# LIA_slave.net
KiCad netlist of a schematic drawn in Altium Designer
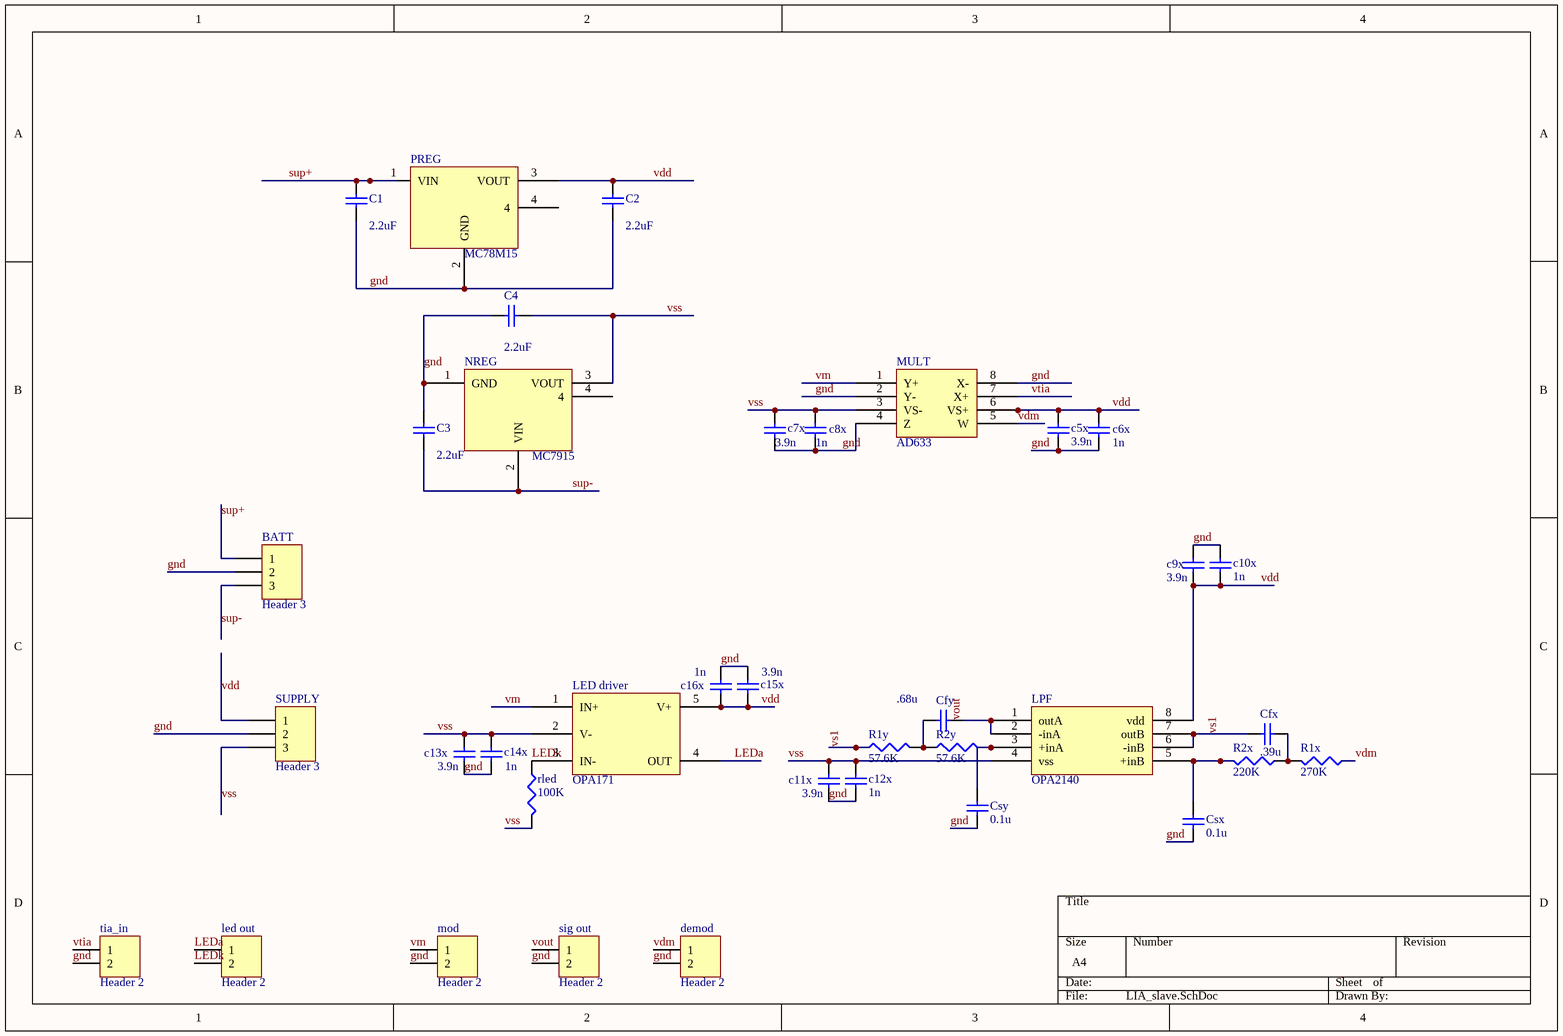
[diagram p0: LIA_slave.SchDoc]

(export (version "E")
  (design (tool "Eeschema 10.0.6"))
  (components
    (comp (ref "BATT")
      (value "Header 3")
      (footprint "HDR1X3")
      (description "Header, 3-Pin")
      (fields (field (name "PUBLISHER") "Altium Limited"))
      (libsource (lib "Miscellaneous Connectors") (part "Header 3"))
    )
    (comp (ref "C1")
      (value "2.2uF")
      (footprint "0402")
      (description "Ceramic Chip Capacitor - Standard")
      (fields (field (name "Comment") "GRM155R61C225KE11D") (field (name "PUBLISHER") "Altium Limited"))
      (libsource (lib "KEMET Chip Capacitor") (part "C0402"))
    )
    (comp (ref "C2")
      (value "2.2uF")
      (footprint "0402")
      (description "Ceramic Chip Capacitor - Standard")
      (fields (field (name "Comment") "GRM155R61C225KE11D") (field (name "PUBLISHER") "Altium Limited"))
      (libsource (lib "KEMET Chip Capacitor") (part "C0402"))
    )
    (comp (ref "C3")
      (value "2.2uF")
      (footprint "0402")
      (description "Ceramic Chip Capacitor - Standard")
      (fields (field (name "Comment") "GRM155R61C225KE11D") (field (name "PUBLISHER") "Altium Limited"))
      (libsource (lib "KEMET Chip Capacitor") (part "C0402"))
    )
    (comp (ref "C4")
      (value "2.2uF")
      (footprint "0402")
      (description "Ceramic Chip Capacitor - Standard")
      (fields (field (name "Comment") "GRM155R61C225KE11D") (field (name "PUBLISHER") "Altium Limited"))
      (libsource (lib "KEMET Chip Capacitor") (part "C0402"))
    )
    (comp (ref "c5x")
      (value "3.9n")
      (footprint "0402")
      (description "Ceramic Chip Capacitor - Standard")
      (fields (field (name "Comment") "GRM155R71H392KA01D") (field (name "PUBLISHER") "Altium Limited"))
      (libsource (lib "KEMET Chip Capacitor") (part "C0402"))
    )
    (comp (ref "c6x")
      (value "1n")
      (footprint "0402")
      (description "Ceramic Chip Capacitor - Standard")
      (fields (field (name "Comment") "GRM155R71H102KA01D") (field (name "PUBLISHER") "Altium Limited"))
      (libsource (lib "KEMET Chip Capacitor") (part "C0402"))
    )
    (comp (ref "c7x")
      (value "3.9n")
      (footprint "0402")
      (description "Ceramic Chip Capacitor - Standard")
      (fields (field (name "Comment") "GRM155R71H392KA01D") (field (name "PUBLISHER") "Altium Limited"))
      (libsource (lib "KEMET Chip Capacitor") (part "C0402"))
    )
    (comp (ref "c8x")
      (value "1n")
      (footprint "0402")
      (description "Ceramic Chip Capacitor - Standard")
      (fields (field (name "Comment") "GRM155R71H102KA01D") (field (name "PUBLISHER") "Altium Limited"))
      (libsource (lib "KEMET Chip Capacitor") (part "C0402"))
    )
    (comp (ref "c9x")
      (value "3.9n")
      (footprint "0402")
      (description "Ceramic Chip Capacitor - Standard")
      (fields (field (name "Comment") "GRM155R71H392KA01D") (field (name "PUBLISHER") "Altium Limited"))
      (libsource (lib "KEMET Chip Capacitor") (part "C0402"))
    )
    (comp (ref "c10x")
      (value "1n")
      (footprint "0402")
      (description "Ceramic Chip Capacitor - Standard")
      (fields (field (name "Comment") "GRM155R71H102KA01D") (field (name "PUBLISHER") "Altium Limited"))
      (libsource (lib "KEMET Chip Capacitor") (part "C0402"))
    )
    (comp (ref "c11x")
      (value "3.9n")
      (footprint "0402")
      (description "Ceramic Chip Capacitor - Standard")
      (fields (field (name "Comment") "GRM155R71H392KA01D") (field (name "PUBLISHER") "Altium Limited"))
      (libsource (lib "KEMET Chip Capacitor") (part "C0402"))
    )
    (comp (ref "c12x")
      (value "1n")
      (footprint "0402")
      (description "Ceramic Chip Capacitor - Standard")
      (fields (field (name "Comment") "GRM155R71H102KA01D") (field (name "PUBLISHER") "Altium Limited"))
      (libsource (lib "KEMET Chip Capacitor") (part "C0402"))
    )
    (comp (ref "c13x")
      (value "3.9n")
      (footprint "0402")
      (description "Ceramic Chip Capacitor - Standard")
      (fields (field (name "Comment") "GRM155R71H392KA01D") (field (name "PUBLISHER") "Altium Limited"))
      (libsource (lib "KEMET Chip Capacitor") (part "C0402"))
    )
    (comp (ref "c14x")
      (value "1n")
      (footprint "0402")
      (description "Ceramic Chip Capacitor - Standard")
      (fields (field (name "Comment") "GRM155R71H102KA01D") (field (name "PUBLISHER") "Altium Limited"))
      (libsource (lib "KEMET Chip Capacitor") (part "C0402"))
    )
    (comp (ref "c15x")
      (value "3.9n")
      (footprint "0402")
      (description "Ceramic Chip Capacitor - Standard")
      (fields (field (name "Comment") "GRM155R71H392KA01D") (field (name "PUBLISHER") "Altium Limited"))
      (libsource (lib "KEMET Chip Capacitor") (part "C0402"))
    )
    (comp (ref "c16x")
      (value "1n")
      (footprint "0402")
      (description "Ceramic Chip Capacitor - Standard")
      (fields (field (name "Comment") "GRM155R71H102KA01D") (field (name "PUBLISHER") "Altium Limited"))
      (libsource (lib "KEMET Chip Capacitor") (part "C0402"))
    )
    (comp (ref "Cfx")
      (value ".39u")
      (footprint "0402")
      (description "Ceramic Chip Capacitor - Standard")
      (fields (field (name "Comment") "GRM155R61A394KE15D") (field (name "PUBLISHER") "Altium Limited"))
      (libsource (lib "KEMET Chip Capacitor") (part "C0402"))
    )
    (comp (ref "Cfy")
      (value ".68u")
      (footprint "0402")
      (description "Ceramic Chip Capacitor - Standard")
      (fields (field (name "Comment") "C1005X5R1C684K050BC") (field (name "PUBLISHER") "Altium Limited"))
      (libsource (lib "KEMET Chip Capacitor") (part "C0402"))
    )
    (comp (ref "Csx")
      (value "0.1u")
      (footprint "0402")
      (description "Ceramic Chip Capacitor - Standard")
      (fields (field (name "Comment") "GRM155R61C104KA88J") (field (name "PUBLISHER") "Altium Limited"))
      (libsource (lib "KEMET Chip Capacitor") (part "C0402"))
    )
    (comp (ref "Csy")
      (value "0.1u")
      (footprint "0402")
      (description "Ceramic Chip Capacitor - Standard")
      (fields (field (name "Comment") "GRM155R61C104KA88J") (field (name "PUBLISHER") "Altium Limited"))
      (libsource (lib "KEMET Chip Capacitor") (part "C0402"))
    )
    (comp (ref "demod")
      (value "Header 2")
      (footprint "HDR1X2")
      (description "Header, 2-Pin")
      (fields (field (name "PUBLISHER") "Altium Limited"))
      (libsource (lib "Miscellaneous Connectors") (part "Header 2"))
    )
    (comp (ref "LED driver")
      (value "OPA171")
      (footprint "S5")
      (description "Single supply opamp SOT 553")
      (libsource (lib "katschematic") (part "OPA171"))
    )
    (comp (ref "led out")
      (value "Header 2")
      (footprint "HDR1X2")
      (description "Header, 2-Pin")
      (fields (field (name "PUBLISHER") "Altium Limited"))
      (libsource (lib "Miscellaneous Connectors") (part "Header 2"))
    )
    (comp (ref "LPF")
      (value "OPA2140")
      (description "dual channel JFET op amp")
      (libsource (lib "Schlib1") (part "OPA2211"))
    )
    (comp (ref "mod")
      (value "Header 2")
      (footprint "HDR1X2")
      (description "Header, 2-Pin")
      (fields (field (name "PUBLISHER") "Altium Limited"))
      (libsource (lib "Miscellaneous Connectors") (part "Header 2"))
    )
    (comp (ref "MULT")
      (value "AD633")
      (footprint "D008_L")
      (description "Analog multiplier")
      (libsource (lib "katschematic") (part "AD633"))
    )
    (comp (ref "NREG")
      (value "MC7915")
      (footprint "D2PAK_L")
      (description "-15 V LDO regulator")
      (libsource (lib "katschematic") (part "MC7915"))
    )
    (comp (ref "PREG")
      (value "MC78M15")
      (footprint "D2PAK_L")
      (description "+15 V LDO regulator")
      (libsource (lib "katschematic") (part "MC78M15"))
    )
    (comp (ref "R1x")
      (value "270K")
      (footprint "J1-0603")
      (description "Resistor")
      (fields (field (name "Comment") "RC0603FR-07270KL") (field (name "PUBLISHER") "Altium Limited"))
      (libsource (lib "Miscellaneous Devices") (part "Res3"))
    )
    (comp (ref "R1y")
      (value "57.6K")
      (footprint "J1-0603")
      (description "Resistor")
      (fields (field (name "Comment") "RC0603FR-0757K6L") (field (name "PUBLISHER") "Altium Limited"))
      (libsource (lib "Miscellaneous Devices") (part "Res3"))
    )
    (comp (ref "R2x")
      (value "220K")
      (footprint "J1-0603")
      (description "Resistor")
      (fields (field (name "Comment") "RC0603FR-07220KL") (field (name "PUBLISHER") "Altium Limited"))
      (libsource (lib "Miscellaneous Devices") (part "Res3"))
    )
    (comp (ref "R2y")
      (value "57.6K")
      (footprint "J1-0603")
      (description "Resistor")
      (fields (field (name "Comment") "RC0603FR-0757K6L") (field (name "PUBLISHER") "Altium Limited"))
      (libsource (lib "Miscellaneous Devices") (part "Res3"))
    )
    (comp (ref "rled")
      (value "100K")
      (footprint "J1-0603")
      (description "Resistor")
      (fields (field (name "Comment") "RC0603FR-07100KL") (field (name "PUBLISHER") "Altium Limited"))
      (libsource (lib "Miscellaneous Devices") (part "Res3"))
    )
    (comp (ref "sig out")
      (value "Header 2")
      (footprint "HDR1X2")
      (description "Header, 2-Pin")
      (fields (field (name "PUBLISHER") "Altium Limited"))
      (libsource (lib "Miscellaneous Connectors") (part "Header 2"))
    )
    (comp (ref "SUPPLY")
      (value "Header 3")
      (footprint "HDR1X3")
      (description "Header, 3-Pin")
      (fields (field (name "PUBLISHER") "Altium Limited"))
      (libsource (lib "Miscellaneous Connectors") (part "Header 3"))
    )
    (comp (ref "tia_in")
      (value "Header 2")
      (footprint "HDR1X2")
      (description "Header, 2-Pin")
      (fields (field (name "PUBLISHER") "Altium Limited"))
      (libsource (lib "Miscellaneous Connectors") (part "Header 2"))
    )
  )
  (nets
    (net (code "1") (name "/LEDa") (class "Default")
      (node (ref "LED driver") (pin "4") (pinfunction "OUT_4") (pintype "passive"))
      (node (ref "led out") (pin "1") (pinfunction "1_1") (pintype "passive"))
    )
    (net (code "2") (name "/LEDk") (class "Default")
      (node (ref "LED driver") (pin "3") (pinfunction "IN-_3") (pintype "passive"))
      (node (ref "led out") (pin "2") (pinfunction "2_2") (pintype "passive"))
      (node (ref "rled") (pin "1") (pinfunction "1_1") (pintype "passive"))
    )
    (net (code "3") (name "/gnd") (class "Default")
      (node (ref "BATT") (pin "2") (pinfunction "2_2") (pintype "passive"))
      (node (ref "C1") (pin "1") (pinfunction "1_1") (pintype "passive"))
      (node (ref "C2") (pin "1") (pinfunction "1_1") (pintype "passive"))
      (node (ref "C3") (pin "1") (pinfunction "1_1") (pintype "passive"))
      (node (ref "C4") (pin "1") (pinfunction "1_1") (pintype "passive"))
      (node (ref "Csx") (pin "1") (pinfunction "1_1") (pintype "passive"))
      (node (ref "Csy") (pin "1") (pinfunction "1_1") (pintype "passive"))
      (node (ref "MULT") (pin "2") (pinfunction "Y-_2") (pintype "passive"))
      (node (ref "MULT") (pin "4") (pinfunction "Z_4") (pintype "passive"))
      (node (ref "MULT") (pin "8") (pinfunction "X-_8") (pintype "passive"))
      (node (ref "NREG") (pin "1") (pinfunction "GND_1") (pintype "passive"))
      (node (ref "PREG") (pin "2") (pinfunction "GND_2") (pintype "passive"))
      (node (ref "SUPPLY") (pin "2") (pinfunction "2_2") (pintype "passive"))
      (node (ref "c10x") (pin "2") (pinfunction "2_2") (pintype "passive"))
      (node (ref "c11x") (pin "2") (pinfunction "2_2") (pintype "passive"))
      (node (ref "c12x") (pin "2") (pinfunction "2_2") (pintype "passive"))
      (node (ref "c13x") (pin "2") (pinfunction "2_2") (pintype "passive"))
      (node (ref "c14x") (pin "2") (pinfunction "2_2") (pintype "passive"))
      (node (ref "c15x") (pin "2") (pinfunction "2_2") (pintype "passive"))
      (node (ref "c16x") (pin "2") (pinfunction "2_2") (pintype "passive"))
      (node (ref "c5x") (pin "1") (pinfunction "1_1") (pintype "passive"))
      (node (ref "c6x") (pin "1") (pinfunction "1_1") (pintype "passive"))
      (node (ref "c7x") (pin "1") (pinfunction "1_1") (pintype "passive"))
      (node (ref "c8x") (pin "1") (pinfunction "1_1") (pintype "passive"))
      (node (ref "c9x") (pin "2") (pinfunction "2_2") (pintype "passive"))
      (node (ref "demod") (pin "2") (pinfunction "2_2") (pintype "passive"))
      (node (ref "mod") (pin "2") (pinfunction "2_2") (pintype "passive"))
      (node (ref "sig out") (pin "2") (pinfunction "2_2") (pintype "passive"))
      (node (ref "tia_in") (pin "2") (pinfunction "2_2") (pintype "passive"))
    )
    (net (code "4") (name "/sup+") (class "Default")
      (node (ref "BATT") (pin "1") (pinfunction "1_1") (pintype "passive"))
      (node (ref "C1") (pin "2") (pinfunction "2_2") (pintype "passive"))
      (node (ref "PREG") (pin "1") (pinfunction "VIN_1") (pintype "passive"))
    )
    (net (code "5") (name "/sup-") (class "Default")
      (node (ref "BATT") (pin "3") (pinfunction "3_3") (pintype "passive"))
      (node (ref "C3") (pin "2") (pinfunction "2_2") (pintype "passive"))
      (node (ref "NREG") (pin "2") (pinfunction "VIN_2") (pintype "passive"))
    )
    (net (code "6") (name "/vdd") (class "Default")
      (node (ref "C2") (pin "2") (pinfunction "2_2") (pintype "passive"))
      (node (ref "LED driver") (pin "5") (pinfunction "V+_5") (pintype "passive"))
      (node (ref "LPF") (pin "8") (pinfunction "vdd_8") (pintype "passive"))
      (node (ref "MULT") (pin "6") (pinfunction "VS+_6") (pintype "passive"))
      (node (ref "PREG") (pin "3") (pinfunction "VOUT_3") (pintype "passive"))
      (node (ref "SUPPLY") (pin "1") (pinfunction "1_1") (pintype "passive"))
      (node (ref "c10x") (pin "1") (pinfunction "1_1") (pintype "passive"))
      (node (ref "c15x") (pin "1") (pinfunction "1_1") (pintype "passive"))
      (node (ref "c16x") (pin "1") (pinfunction "1_1") (pintype "passive"))
      (node (ref "c5x") (pin "2") (pinfunction "2_2") (pintype "passive"))
      (node (ref "c6x") (pin "2") (pinfunction "2_2") (pintype "passive"))
      (node (ref "c9x") (pin "1") (pinfunction "1_1") (pintype "passive"))
    )
    (net (code "7") (name "/vdm") (class "Default")
      (node (ref "MULT") (pin "5") (pinfunction "W_5") (pintype "passive"))
      (node (ref "R1x") (pin "1") (pinfunction "1_1") (pintype "passive"))
      (node (ref "demod") (pin "1") (pinfunction "1_1") (pintype "passive"))
    )
    (net (code "8") (name "/vm") (class "Default")
      (node (ref "LED driver") (pin "1") (pinfunction "IN+_1") (pintype "passive"))
      (node (ref "MULT") (pin "1") (pinfunction "Y+_1") (pintype "passive"))
      (node (ref "mod") (pin "1") (pinfunction "1_1") (pintype "passive"))
    )
    (net (code "9") (name "/vout") (class "Default")
      (node (ref "Cfy") (pin "1") (pinfunction "1_1") (pintype "passive"))
      (node (ref "LPF") (pin "1") (pinfunction "outA_1") (pintype "passive"))
      (node (ref "LPF") (pin "2") (pinfunction "-inA_2") (pintype "passive"))
      (node (ref "sig out") (pin "1") (pinfunction "1_1") (pintype "passive"))
    )
    (net (code "10") (name "/vs1") (class "Default")
      (node (ref "Cfx") (pin "2") (pinfunction "2_2") (pintype "passive"))
      (node (ref "LPF") (pin "6") (pinfunction "-inB_6") (pintype "passive"))
      (node (ref "LPF") (pin "7") (pinfunction "outB_7") (pintype "passive"))
      (node (ref "R1y") (pin "1") (pinfunction "1_1") (pintype "passive"))
    )
    (net (code "11") (name "/vss") (class "Default")
      (node (ref "C4") (pin "2") (pinfunction "2_2") (pintype "passive"))
      (node (ref "LED driver") (pin "2") (pinfunction "V-_2") (pintype "passive"))
      (node (ref "LPF") (pin "4") (pinfunction "vss_4") (pintype "passive"))
      (node (ref "MULT") (pin "3") (pinfunction "VS-_3") (pintype "passive"))
      (node (ref "NREG") (pin "3") (pinfunction "VOUT_3") (pintype "passive"))
      (node (ref "SUPPLY") (pin "3") (pinfunction "3_3") (pintype "passive"))
      (node (ref "c11x") (pin "1") (pinfunction "1_1") (pintype "passive"))
      (node (ref "c12x") (pin "1") (pinfunction "1_1") (pintype "passive"))
      (node (ref "c13x") (pin "1") (pinfunction "1_1") (pintype "passive"))
      (node (ref "c14x") (pin "1") (pinfunction "1_1") (pintype "passive"))
      (node (ref "c7x") (pin "2") (pinfunction "2_2") (pintype "passive"))
      (node (ref "c8x") (pin "2") (pinfunction "2_2") (pintype "passive"))
      (node (ref "rled") (pin "2") (pinfunction "2_2") (pintype "passive"))
    )
    (net (code "12") (name "/vtia") (class "Default")
      (node (ref "MULT") (pin "7") (pinfunction "X+_7") (pintype "passive"))
      (node (ref "tia_in") (pin "1") (pinfunction "1_1") (pintype "passive"))
    )
    (net (code "13") (name "Net-(Cfx-Pad1)") (class "Default")
      (node (ref "Cfx") (pin "1") (pinfunction "1_1") (pintype "passive"))
      (node (ref "R1x") (pin "2") (pinfunction "2_2") (pintype "passive"))
      (node (ref "R2x") (pin "1") (pinfunction "1_1") (pintype "passive"))
    )
    (net (code "14") (name "Net-(Cfy-Pad2)") (class "Default")
      (node (ref "Cfy") (pin "2") (pinfunction "2_2") (pintype "passive"))
      (node (ref "R1y") (pin "2") (pinfunction "2_2") (pintype "passive"))
      (node (ref "R2y") (pin "1") (pinfunction "1_1") (pintype "passive"))
    )
    (net (code "15") (name "Net-(LPF-+inA)") (class "Default")
      (node (ref "Csy") (pin "2") (pinfunction "2_2") (pintype "passive"))
      (node (ref "LPF") (pin "3") (pinfunction "+inA_3") (pintype "passive"))
      (node (ref "R2y") (pin "2") (pinfunction "2_2") (pintype "passive"))
    )
    (net (code "16") (name "Net-(LPF-+inB)") (class "Default")
      (node (ref "Csx") (pin "2") (pinfunction "2_2") (pintype "passive"))
      (node (ref "LPF") (pin "5") (pinfunction "+inB_5") (pintype "passive"))
      (node (ref "R2x") (pin "2") (pinfunction "2_2") (pintype "passive"))
    )
    (net (code "17") (name "unconnected-(NREG-Pad4)") (class "Default")
      (node (ref "NREG") (pin "4") (pinfunction "4_4") (pintype "passive"))
    )
    (net (code "18") (name "unconnected-(PREG-Pad4)") (class "Default")
      (node (ref "PREG") (pin "4") (pinfunction "4_4") (pintype "passive"))
    )
  )
)
